# MySensors_AirQuality_Board_2017-11-26_an.net
KiCad netlist of a schematic drawn in EAGLE
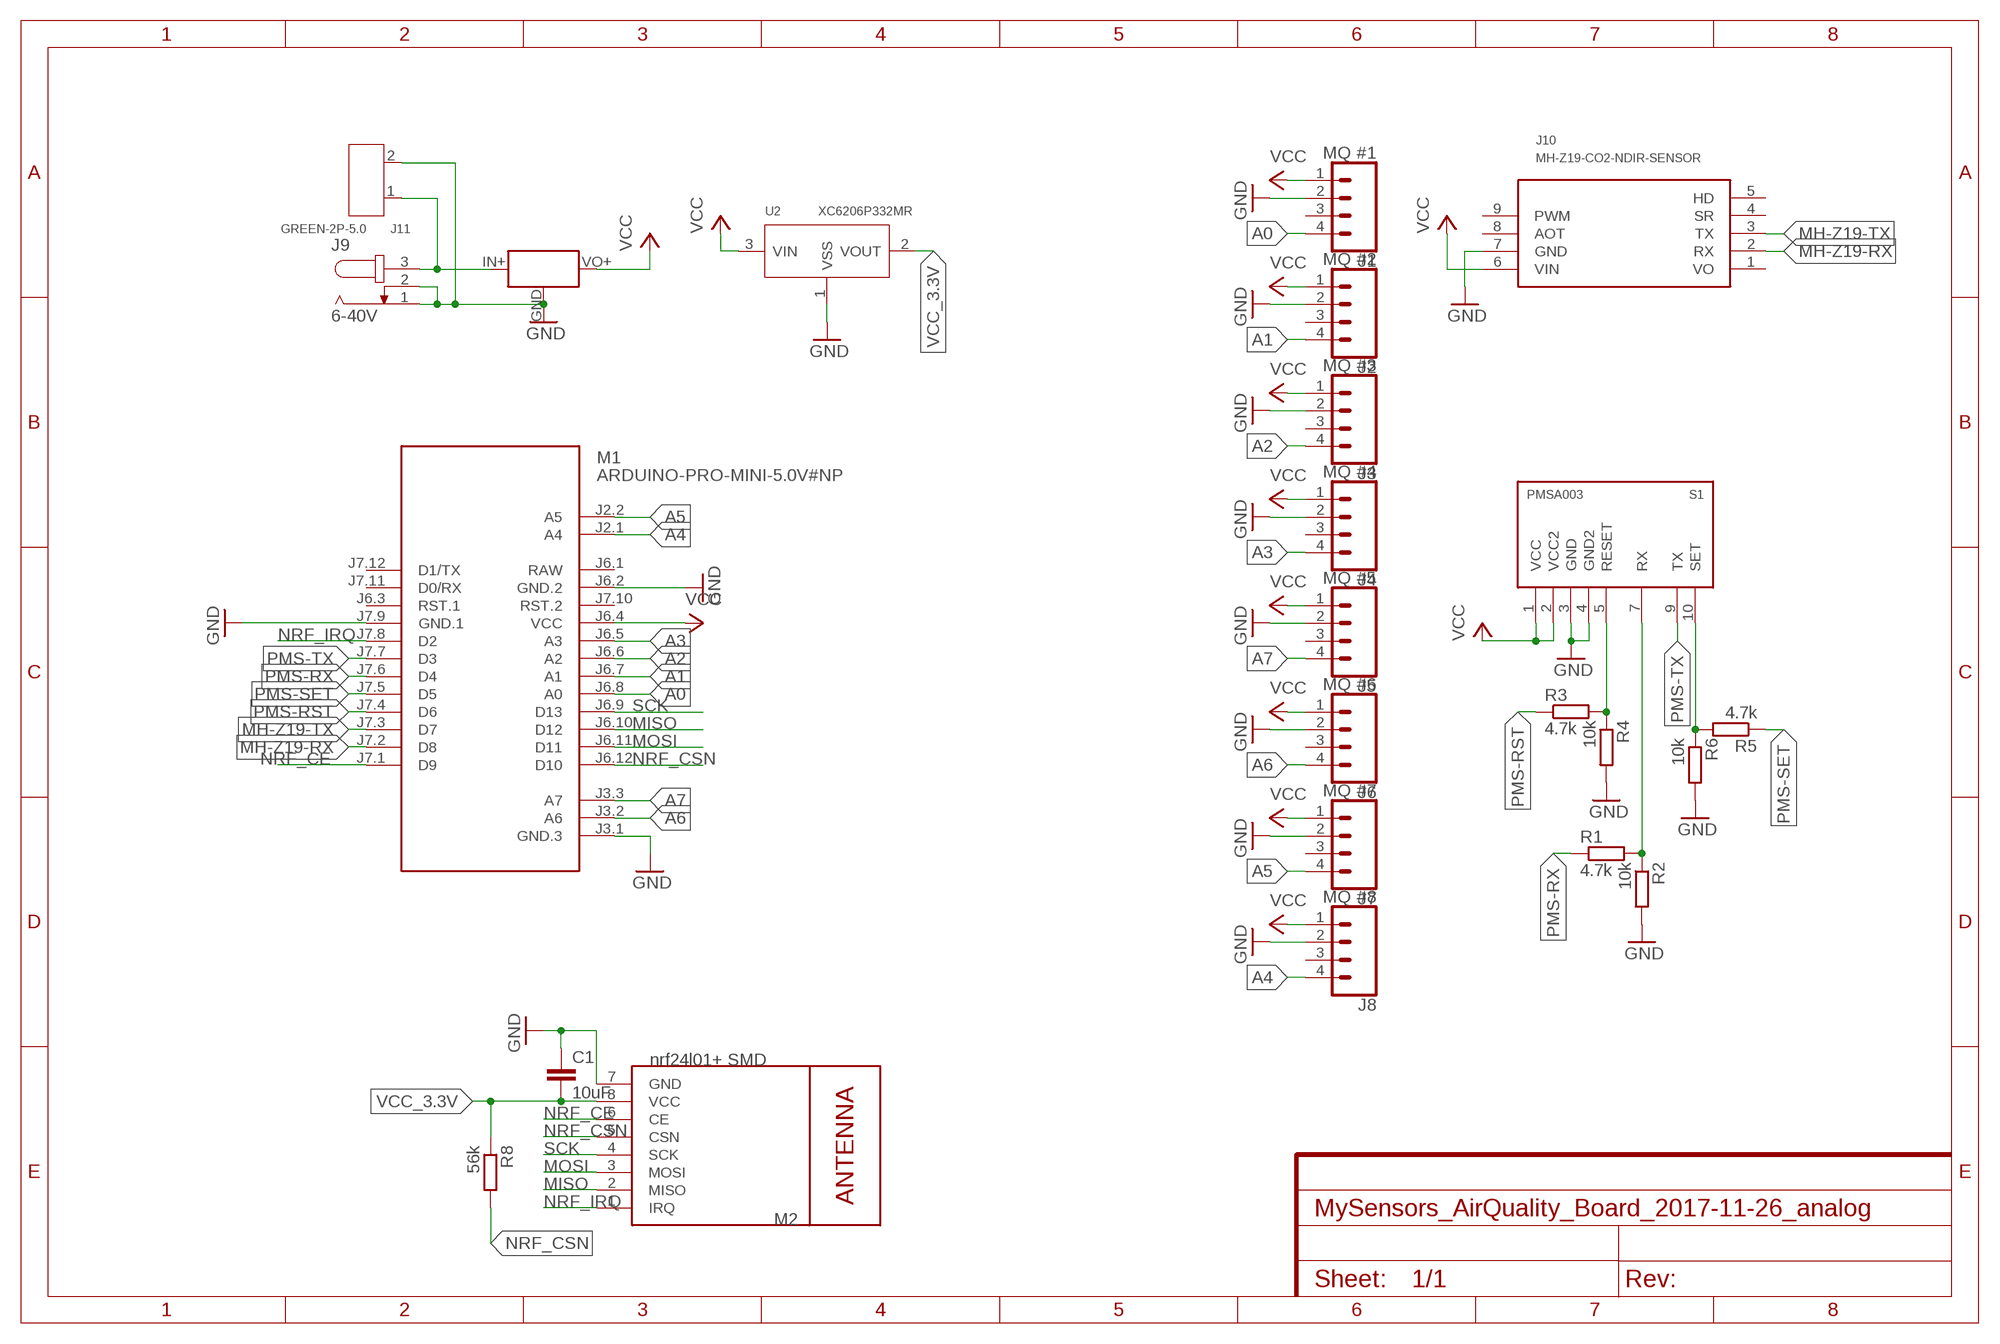
[diagram p0: schematic, sheet 1]

(export (version "E")
  (design (tool "Eeschema 10.0.6"))
  (components
    (comp (ref "C1")
      (value "10uF")
      (footprint "eagle-import:C0805")
      (libsource (lib "eagle-import") (part "C-EUC0805"))
    )
    (comp (ref "J1")
      (value "MQ #1")
      (footprint "eagle-import:1X04")
      (libsource (lib "eagle-import") (part "CONN_04"))
    )
    (comp (ref "J2")
      (value "MQ #2")
      (footprint "eagle-import:1X04")
      (libsource (lib "eagle-import") (part "CONN_04"))
    )
    (comp (ref "J3")
      (value "MQ #3")
      (footprint "eagle-import:1X04")
      (libsource (lib "eagle-import") (part "CONN_04"))
    )
    (comp (ref "J4")
      (value "MQ #4")
      (footprint "eagle-import:1X04")
      (libsource (lib "eagle-import") (part "CONN_04"))
    )
    (comp (ref "J5")
      (value "MQ #5")
      (footprint "eagle-import:1X04")
      (libsource (lib "eagle-import") (part "CONN_04"))
    )
    (comp (ref "J6")
      (value "MQ #6")
      (footprint "eagle-import:1X04")
      (libsource (lib "eagle-import") (part "CONN_04"))
    )
    (comp (ref "J7")
      (value "MQ #7")
      (footprint "eagle-import:1X04")
      (libsource (lib "eagle-import") (part "CONN_04"))
    )
    (comp (ref "J8")
      (value "MQ #8")
      (footprint "eagle-import:1X04")
      (libsource (lib "eagle-import") (part "CONN_04"))
    )
    (comp (ref "J9")
      (value "6-40V")
      (footprint "eagle-import:SPC4078")
      (libsource (lib "eagle-import") (part "JACK-PLUG1"))
    )
    (comp (ref "J10")
      (value "MH-Z19-CO2-NDIR-SENSOR")
      (footprint "eagle-import:MH-Z19")
      (libsource (lib "eagle-import") (part "MH-Z19-CO2-NDIR-SENSOR"))
    )
    (comp (ref "J11")
      (value "GREEN-2P-5.0")
      (footprint "eagle-import:H2-5.0-10.5X8.0MM")
      (libsource (lib "eagle-import") (part "SCREW-TERMINAL-GREEN(2P-5.0)"))
    )
    (comp (ref "M1")
      (value "ARDUINO-PRO-MINI-5.0V#NP")
      (footprint "eagle-import:ARDUINO-PRO-MINI#NP")
      (libsource (lib "eagle-import") (part "ARDUINO-PRO-MINI-#NP5.0V"))
    )
    (comp (ref "M2")
      (value "nrf24l01+ SMD")
      (footprint "eagle-import:WIRELESS-NRF24L01-SMD")
      (libsource (lib "eagle-import") (part "WIRELESS-NRF24L01SMD"))
    )
    (comp (ref "R1")
      (value "4.7k")
      (footprint "eagle-import:R0805")
      (libsource (lib "eagle-import") (part "resistor_348_R-EU_R0805"))
    )
    (comp (ref "R2")
      (value "10k")
      (footprint "eagle-import:R0805")
      (libsource (lib "eagle-import") (part "resistor_348_R-EU_R0805"))
    )
    (comp (ref "R3")
      (value "4.7k")
      (footprint "eagle-import:R0805")
      (libsource (lib "eagle-import") (part "resistor_348_R-EU_R0805"))
    )
    (comp (ref "R4")
      (value "10k")
      (footprint "eagle-import:R0805")
      (libsource (lib "eagle-import") (part "resistor_348_R-EU_R0805"))
    )
    (comp (ref "R5")
      (value "4.7k")
      (footprint "eagle-import:R0805")
      (libsource (lib "eagle-import") (part "resistor_348_R-EU_R0805"))
    )
    (comp (ref "R6")
      (value "10k")
      (footprint "eagle-import:R0805")
      (libsource (lib "eagle-import") (part "resistor_348_R-EU_R0805"))
    )
    (comp (ref "R8")
      (value "56k")
      (footprint "eagle-import:R0805")
      (libsource (lib "eagle-import") (part "R-EU_R0805"))
    )
    (comp (ref "S1")
      (value "PMSA003")
      (footprint "eagle-import:PMSA003")
      (libsource (lib "eagle-import") (part "PMSA003"))
    )
    (comp (ref "U$2")
      (value "MINI_BUCK_CONVERTER")
      (footprint "eagle-import:MINI_BUCK_CONVERTER")
      (libsource (lib "eagle-import") (part "MINI_BUCK_CONVERTER"))
    )
    (comp (ref "U2")
      (value "XC6206P332MR")
      (footprint "eagle-import:SOT-23")
      (fields (field (name "MPN") "XC6206P332MR-G"))
      (libsource (lib "eagle-import") (part "PMIC-LDO-XC6206P332MR-G(SOT23)"))
    )
  )
  (nets
    (net (code "1") (name "/MISO") (class "Default")
      (node (ref "M1") (pin "J6.10") (pinfunction "D12_J6.10") (pintype "bidirectional"))
      (node (ref "M2") (pin "2") (pinfunction "MISO_2") (pintype "bidirectional"))
    )
    (net (code "2") (name "/MOSI") (class "Default")
      (node (ref "M1") (pin "J6.11") (pinfunction "D11_J6.11") (pintype "bidirectional"))
      (node (ref "M2") (pin "3") (pinfunction "MOSI_3") (pintype "bidirectional"))
    )
    (net (code "3") (name "/NRF_CE") (class "Default")
      (node (ref "M1") (pin "J7.1") (pinfunction "D9_J7.1") (pintype "bidirectional"))
      (node (ref "M2") (pin "6") (pinfunction "CE_6") (pintype "bidirectional"))
    )
    (net (code "4") (name "/NRF_IRQ") (class "Default")
      (node (ref "M1") (pin "J7.8") (pinfunction "D2_J7.8") (pintype "bidirectional"))
      (node (ref "M2") (pin "1") (pinfunction "IRQ_1") (pintype "bidirectional"))
    )
    (net (code "5") (name "/RAW") (class "Default")
      (node (ref "M1") (pin "J6.1") (pinfunction "RAW_J6.1") (pintype "power_in"))
    )
    (net (code "6") (name "/SCK") (class "Default")
      (node (ref "M1") (pin "J6.9") (pinfunction "D13_J6.9") (pintype "bidirectional"))
      (node (ref "M2") (pin "4") (pinfunction "SCK_4") (pintype "bidirectional"))
    )
    (net (code "7") (name "/VO") (class "Default")
      (node (ref "J10") (pin "1") (pinfunction "VO_1") (pintype "power_in"))
    )
    (net (code "8") (name "A0") (class "Default")
      (node (ref "J1") (pin "4") (pinfunction "4_4") (pintype "passive"))
      (node (ref "M1") (pin "J6.8") (pinfunction "A0_J6.8") (pintype "bidirectional"))
    )
    (net (code "9") (name "A1") (class "Default")
      (node (ref "J2") (pin "4") (pinfunction "4_4") (pintype "passive"))
      (node (ref "M1") (pin "J6.7") (pinfunction "A1_J6.7") (pintype "bidirectional"))
    )
    (net (code "10") (name "A2") (class "Default")
      (node (ref "J3") (pin "4") (pinfunction "4_4") (pintype "passive"))
      (node (ref "M1") (pin "J6.6") (pinfunction "A2_J6.6") (pintype "bidirectional"))
    )
    (net (code "11") (name "A3") (class "Default")
      (node (ref "J4") (pin "4") (pinfunction "4_4") (pintype "passive"))
      (node (ref "M1") (pin "J6.5") (pinfunction "A3_J6.5") (pintype "bidirectional"))
    )
    (net (code "12") (name "A4") (class "Default")
      (node (ref "J8") (pin "4") (pinfunction "4_4") (pintype "passive"))
      (node (ref "M1") (pin "J2.1") (pinfunction "A4_J2.1") (pintype "bidirectional"))
    )
    (net (code "13") (name "A5") (class "Default")
      (node (ref "J7") (pin "4") (pinfunction "4_4") (pintype "passive"))
      (node (ref "M1") (pin "J2.2") (pinfunction "A5_J2.2") (pintype "bidirectional"))
    )
    (net (code "14") (name "A6") (class "Default")
      (node (ref "J6") (pin "4") (pinfunction "4_4") (pintype "passive"))
      (node (ref "M1") (pin "J3.2") (pinfunction "A6_J3.2") (pintype "bidirectional"))
    )
    (net (code "15") (name "A7") (class "Default")
      (node (ref "J5") (pin "4") (pinfunction "4_4") (pintype "passive"))
      (node (ref "M1") (pin "J3.3") (pinfunction "A7_J3.3") (pintype "bidirectional"))
    )
    (net (code "16") (name "GND") (class "Default")
      (node (ref "C1") (pin "1") (pinfunction "1_1") (pintype "passive"))
      (node (ref "J1") (pin "2") (pinfunction "2_2") (pintype "passive"))
      (node (ref "J10") (pin "7") (pinfunction "GND_7") (pintype "power_in"))
      (node (ref "J11") (pin "2") (pinfunction "2_2") (pintype "bidirectional"))
      (node (ref "J2") (pin "2") (pinfunction "2_2") (pintype "passive"))
      (node (ref "J3") (pin "2") (pinfunction "2_2") (pintype "passive"))
      (node (ref "J4") (pin "2") (pinfunction "2_2") (pintype "passive"))
      (node (ref "J5") (pin "2") (pinfunction "2_2") (pintype "passive"))
      (node (ref "J6") (pin "2") (pinfunction "2_2") (pintype "passive"))
      (node (ref "J7") (pin "2") (pinfunction "2_2") (pintype "passive"))
      (node (ref "J8") (pin "2") (pinfunction "2_2") (pintype "passive"))
      (node (ref "J9") (pin "1") (pinfunction "1_1") (pintype "passive"))
      (node (ref "J9") (pin "2") (pinfunction "2_2") (pintype "passive"))
      (node (ref "M1") (pin "J3.1") (pinfunction "GND.3_J3.1") (pintype "bidirectional"))
      (node (ref "M1") (pin "J6.2") (pinfunction "GND.2_J6.2") (pintype "power_in"))
      (node (ref "M1") (pin "J7.9") (pinfunction "GND.1_J7.9") (pintype "power_in"))
      (node (ref "M2") (pin "7") (pinfunction "GND_7") (pintype "power_in"))
      (node (ref "R2") (pin "2") (pinfunction "2_2") (pintype "passive"))
      (node (ref "R4") (pin "2") (pinfunction "2_2") (pintype "passive"))
      (node (ref "R6") (pin "2") (pinfunction "2_2") (pintype "passive"))
      (node (ref "S1") (pin "3") (pinfunction "GND_3") (pintype "bidirectional"))
      (node (ref "S1") (pin "4") (pinfunction "GND2_4") (pintype "bidirectional"))
      (node (ref "U$2") (pin "GND") (pinfunction "GND_GND") (pintype "bidirectional"))
      (node (ref "U2") (pin "1") (pinfunction "VSS_1") (pintype "power_in"))
    )
    (net (code "17") (name "MH-Z19-RX") (class "Default")
      (node (ref "J10") (pin "2") (pinfunction "RX_2") (pintype "input"))
      (node (ref "M1") (pin "J7.2") (pinfunction "D8_J7.2") (pintype "bidirectional"))
    )
    (net (code "18") (name "MH-Z19-TX") (class "Default")
      (node (ref "J10") (pin "3") (pinfunction "TX_3") (pintype "output"))
      (node (ref "M1") (pin "J7.3") (pinfunction "D7_J7.3") (pintype "bidirectional"))
    )
    (net (code "19") (name "NRF_CSN") (class "Default")
      (node (ref "M1") (pin "J6.12") (pinfunction "D10_J6.12") (pintype "bidirectional"))
      (node (ref "M2") (pin "5") (pinfunction "CSN_5") (pintype "bidirectional"))
      (node (ref "R8") (pin "2") (pinfunction "2_2") (pintype "passive"))
    )
    (net (code "20") (name "Net-(S1-RESET)") (class "Default")
      (node (ref "R3") (pin "2") (pinfunction "2_2") (pintype "passive"))
      (node (ref "R4") (pin "1") (pinfunction "1_1") (pintype "passive"))
      (node (ref "S1") (pin "5") (pinfunction "RESET_5") (pintype "bidirectional"))
    )
    (net (code "21") (name "Net-(S1-RX)") (class "Default")
      (node (ref "R1") (pin "2") (pinfunction "2_2") (pintype "passive"))
      (node (ref "R2") (pin "1") (pinfunction "1_1") (pintype "passive"))
      (node (ref "S1") (pin "7") (pinfunction "RX_7") (pintype "bidirectional"))
    )
    (net (code "22") (name "Net-(S1-SET)") (class "Default")
      (node (ref "R5") (pin "2") (pinfunction "2_2") (pintype "passive"))
      (node (ref "R6") (pin "1") (pinfunction "1_1") (pintype "passive"))
      (node (ref "S1") (pin "10") (pinfunction "SET_10") (pintype "bidirectional"))
    )
    (net (code "23") (name "Net-(U$2-VIN)") (class "Default")
      (node (ref "J11") (pin "1") (pinfunction "1_1") (pintype "bidirectional"))
      (node (ref "J9") (pin "3") (pinfunction "3_3") (pintype "passive"))
      (node (ref "U$2") (pin "IN+") (pinfunction "VIN_IN+") (pintype "input"))
    )
    (net (code "24") (name "PMS-RST") (class "Default")
      (node (ref "M1") (pin "J7.4") (pinfunction "D6_J7.4") (pintype "bidirectional"))
      (node (ref "R3") (pin "1") (pinfunction "1_1") (pintype "passive"))
    )
    (net (code "25") (name "PMS-RX") (class "Default")
      (node (ref "M1") (pin "J7.6") (pinfunction "D4_J7.6") (pintype "bidirectional"))
      (node (ref "R1") (pin "1") (pinfunction "1_1") (pintype "passive"))
    )
    (net (code "26") (name "PMS-SET") (class "Default")
      (node (ref "M1") (pin "J7.5") (pinfunction "D5_J7.5") (pintype "bidirectional"))
      (node (ref "R5") (pin "1") (pinfunction "1_1") (pintype "passive"))
    )
    (net (code "27") (name "PMS-TX") (class "Default")
      (node (ref "M1") (pin "J7.7") (pinfunction "D3_J7.7") (pintype "bidirectional"))
      (node (ref "S1") (pin "9") (pinfunction "TX_9") (pintype "bidirectional"))
    )
    (net (code "28") (name "VCC") (class "Default")
      (node (ref "J1") (pin "1") (pinfunction "1_1") (pintype "passive"))
      (node (ref "J10") (pin "6") (pinfunction "VIN_6") (pintype "power_in"))
      (node (ref "J2") (pin "1") (pinfunction "1_1") (pintype "passive"))
      (node (ref "J3") (pin "1") (pinfunction "1_1") (pintype "passive"))
      (node (ref "J4") (pin "1") (pinfunction "1_1") (pintype "passive"))
      (node (ref "J5") (pin "1") (pinfunction "1_1") (pintype "passive"))
      (node (ref "J6") (pin "1") (pinfunction "1_1") (pintype "passive"))
      (node (ref "J7") (pin "1") (pinfunction "1_1") (pintype "passive"))
      (node (ref "J8") (pin "1") (pinfunction "1_1") (pintype "passive"))
      (node (ref "M1") (pin "J6.4") (pinfunction "VCC_J6.4") (pintype "power_in"))
      (node (ref "S1") (pin "1") (pinfunction "VCC_1") (pintype "bidirectional"))
      (node (ref "S1") (pin "2") (pinfunction "VCC2_2") (pintype "bidirectional"))
      (node (ref "U$2") (pin "VO+") (pinfunction "VOUT_VO+") (pintype "power_in"))
      (node (ref "U2") (pin "3") (pinfunction "VIN_3") (pintype "input"))
    )
    (net (code "29") (name "VCC_3.3V") (class "Default")
      (node (ref "C1") (pin "2") (pinfunction "2_2") (pintype "passive"))
      (node (ref "M2") (pin "8") (pinfunction "VCC_8") (pintype "power_in"))
      (node (ref "R8") (pin "1") (pinfunction "1_1") (pintype "passive"))
      (node (ref "U2") (pin "2") (pinfunction "VOUT_2") (pintype "output"))
    )
    (net (code "30") (name "unconnected-(J1-Pad3)") (class "Default")
      (node (ref "J1") (pin "3") (pinfunction "3_3") (pintype "passive"))
    )
    (net (code "31") (name "unconnected-(J2-Pad3)") (class "Default")
      (node (ref "J2") (pin "3") (pinfunction "3_3") (pintype "passive"))
    )
    (net (code "32") (name "unconnected-(J3-Pad3)") (class "Default")
      (node (ref "J3") (pin "3") (pinfunction "3_3") (pintype "passive"))
    )
    (net (code "33") (name "unconnected-(J4-Pad3)") (class "Default")
      (node (ref "J4") (pin "3") (pinfunction "3_3") (pintype "passive"))
    )
    (net (code "34") (name "unconnected-(J5-Pad3)") (class "Default")
      (node (ref "J5") (pin "3") (pinfunction "3_3") (pintype "passive"))
    )
    (net (code "35") (name "unconnected-(J6-Pad3)") (class "Default")
      (node (ref "J6") (pin "3") (pinfunction "3_3") (pintype "passive"))
    )
    (net (code "36") (name "unconnected-(J7-Pad3)") (class "Default")
      (node (ref "J7") (pin "3") (pinfunction "3_3") (pintype "passive"))
    )
    (net (code "37") (name "unconnected-(J8-Pad3)") (class "Default")
      (node (ref "J8") (pin "3") (pinfunction "3_3") (pintype "passive"))
    )
    (net (code "38") (name "unconnected-(J10-AOT-Pad8)") (class "Default")
      (node (ref "J10") (pin "8") (pinfunction "AOT_8") (pintype "no_connect"))
    )
    (net (code "39") (name "unconnected-(J10-HD-Pad5)") (class "Default")
      (node (ref "J10") (pin "5") (pinfunction "HD_5") (pintype "input"))
    )
    (net (code "40") (name "unconnected-(J10-PWM-Pad9)") (class "Default")
      (node (ref "J10") (pin "9") (pinfunction "PWM_9") (pintype "output"))
    )
    (net (code "41") (name "unconnected-(J10-SR-Pad4)") (class "Default")
      (node (ref "J10") (pin "4") (pinfunction "SR_4") (pintype "no_connect"))
    )
    (net (code "42") (name "unconnected-(M1-D0{slash}RX-PadJ7.11)") (class "Default")
      (node (ref "M1") (pin "J7.11") (pinfunction "D0/RX_J7.11") (pintype "bidirectional"))
    )
    (net (code "43") (name "unconnected-(M1-D1{slash}TX-PadJ7.12)") (class "Default")
      (node (ref "M1") (pin "J7.12") (pinfunction "D1/TX_J7.12") (pintype "bidirectional"))
    )
    (net (code "44") (name "unconnected-(M1-RST.1-PadJ6.3)") (class "Default")
      (node (ref "M1") (pin "J6.3") (pinfunction "RST.1_J6.3") (pintype "bidirectional"))
    )
    (net (code "45") (name "unconnected-(M1-RST.2-PadJ7.10)") (class "Default")
      (node (ref "M1") (pin "J7.10") (pinfunction "RST.2_J7.10") (pintype "bidirectional"))
    )
  )
)
